# SCH.net
KiCad netlist of a schematic drawn in Altium Designer
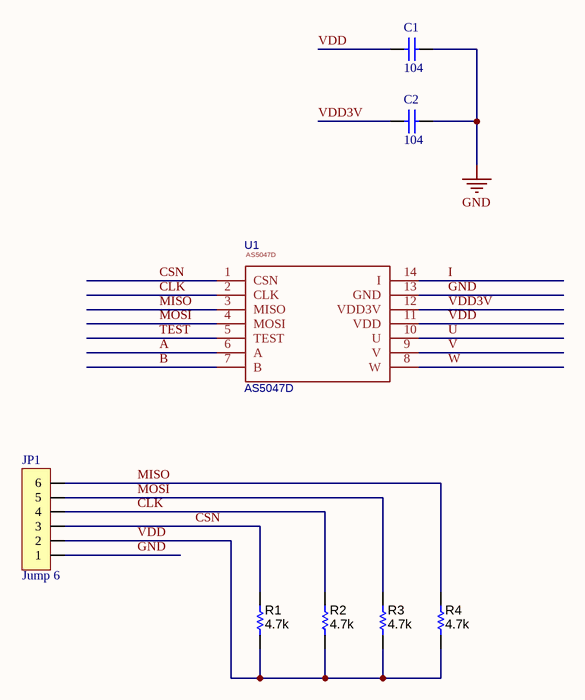
[diagram p0: SCH.SchDoc]

(export (version "E")
  (design (tool "Eeschema 10.0.6"))
  (components
    (comp (ref "C1")
      (value "104")
      (footprint "TU_SMD_0805")
      (description "Ceramic Chip Capacitor - Standard")
      (fields (field (name "PUBLISHER") "Altium Limited"))
      (libsource (lib "mySch") (part "Capacitor 0805"))
    )
    (comp (ref "C2")
      (value "104")
      (footprint "TU_SMD_0805")
      (description "Ceramic Chip Capacitor - Standard")
      (fields (field (name "PUBLISHER") "Altium Limited"))
      (libsource (lib "mySch") (part "Capacitor 0805"))
    )
    (comp (ref "JP1")
      (value "Jump 6")
      (footprint "ZH 1.5 6P")
      (description "Jump 6P 2.54")
      (libsource (lib "mySch") (part "Jump 6"))
    )
    (comp (ref "R1")
      (value "4.7k")
      (footprint "Tro SMD 0805")
      (description "RES, 100, 1%, 0.1 W, 0402")
      (fields
        (field (name "PARTNUMBER") "ERJ-2RKF1000X")
        (field (name "MANUFACTURER") "Panasonic")
        (field (name "PUBLISHER") "Texas Instruments")
      )
      (libsource (lib "mySch") (part "R nho"))
    )
    (comp (ref "R2")
      (value "4.7k")
      (footprint "Tro SMD 0805")
      (description "RES, 100, 1%, 0.1 W, 0402")
      (fields
        (field (name "PARTNUMBER") "ERJ-2RKF1000X")
        (field (name "MANUFACTURER") "Panasonic")
        (field (name "PUBLISHER") "Texas Instruments")
      )
      (libsource (lib "mySch") (part "R nho"))
    )
    (comp (ref "R3")
      (value "4.7k")
      (footprint "Tro SMD 0805")
      (description "RES, 100, 1%, 0.1 W, 0402")
      (fields
        (field (name "PARTNUMBER") "ERJ-2RKF1000X")
        (field (name "MANUFACTURER") "Panasonic")
        (field (name "PUBLISHER") "Texas Instruments")
      )
      (libsource (lib "mySch") (part "R nho"))
    )
    (comp (ref "R4")
      (value "4.7k")
      (footprint "Tro SMD 0805")
      (description "RES, 100, 1%, 0.1 W, 0402")
      (fields
        (field (name "PARTNUMBER") "ERJ-2RKF1000X")
        (field (name "MANUFACTURER") "Panasonic")
        (field (name "PUBLISHER") "Texas Instruments")
      )
      (libsource (lib "mySch") (part "R nho"))
    )
    (comp (ref "U1")
      (value "AS5047D")
      (footprint "TSSOP14")
      (fields (field (name "BOM_MANUFACTURER PART") "?"))
      (libsource (lib "mySch") (part "AS5047D"))
    )
  )
  (nets
    (net (code "1") (name "/A") (class "Default")
      (node (ref "U1") (pin "6") (pinfunction "A_6") (pintype "passive"))
    )
    (net (code "2") (name "/B") (class "Default")
      (node (ref "U1") (pin "7") (pinfunction "B_7") (pintype "passive"))
    )
    (net (code "3") (name "/CLK") (class "Default")
      (node (ref "JP1") (pin "4") (pinfunction "4_4") (pintype "passive"))
      (node (ref "R2") (pin "1") (pinfunction "1_1") (pintype "passive"))
      (node (ref "U1") (pin "2") (pinfunction "CLK_2") (pintype "passive"))
    )
    (net (code "4") (name "/CSN") (class "Default")
      (node (ref "JP1") (pin "3") (pinfunction "3_3") (pintype "passive"))
      (node (ref "R1") (pin "1") (pinfunction "1_1") (pintype "passive"))
      (node (ref "U1") (pin "1") (pinfunction "CSN_1") (pintype "passive"))
    )
    (net (code "5") (name "/I") (class "Default")
      (node (ref "U1") (pin "14") (pinfunction "I_14") (pintype "passive"))
    )
    (net (code "6") (name "/MISO") (class "Default")
      (node (ref "JP1") (pin "6") (pinfunction "6_6") (pintype "passive"))
      (node (ref "R4") (pin "1") (pinfunction "1_1") (pintype "passive"))
      (node (ref "U1") (pin "3") (pinfunction "MISO_3") (pintype "passive"))
    )
    (net (code "7") (name "/MOSI") (class "Default")
      (node (ref "JP1") (pin "5") (pinfunction "5_5") (pintype "passive"))
      (node (ref "R3") (pin "1") (pinfunction "1_1") (pintype "passive"))
      (node (ref "U1") (pin "4") (pinfunction "MOSI_4") (pintype "passive"))
    )
    (net (code "8") (name "/TEST") (class "Default")
      (node (ref "U1") (pin "5") (pinfunction "TEST_5") (pintype "passive"))
    )
    (net (code "9") (name "/U") (class "Default")
      (node (ref "U1") (pin "10") (pinfunction "U_10") (pintype "passive"))
    )
    (net (code "10") (name "/V") (class "Default")
      (node (ref "U1") (pin "9") (pinfunction "V_9") (pintype "passive"))
    )
    (net (code "11") (name "/VDD") (class "Default")
      (node (ref "C1") (pin "1") (pinfunction "1_1") (pintype "passive"))
      (node (ref "JP1") (pin "2") (pinfunction "2_2") (pintype "passive"))
      (node (ref "R1") (pin "2") (pinfunction "2_2") (pintype "passive"))
      (node (ref "R2") (pin "2") (pinfunction "2_2") (pintype "passive"))
      (node (ref "R3") (pin "2") (pinfunction "2_2") (pintype "passive"))
      (node (ref "R4") (pin "2") (pinfunction "2_2") (pintype "passive"))
      (node (ref "U1") (pin "11") (pinfunction "VDD_11") (pintype "passive"))
    )
    (net (code "12") (name "/VDD3V") (class "Default")
      (node (ref "C2") (pin "1") (pinfunction "1_1") (pintype "passive"))
      (node (ref "U1") (pin "12") (pinfunction "VDD3V_12") (pintype "passive"))
    )
    (net (code "13") (name "/W") (class "Default")
      (node (ref "U1") (pin "8") (pinfunction "W_8") (pintype "passive"))
    )
    (net (code "14") (name "GND") (class "Default")
      (node (ref "C1") (pin "2") (pinfunction "2_2") (pintype "passive"))
      (node (ref "C2") (pin "2") (pinfunction "2_2") (pintype "passive"))
      (node (ref "JP1") (pin "1") (pinfunction "1_1") (pintype "passive"))
      (node (ref "U1") (pin "13") (pinfunction "GND_13") (pintype "passive"))
    )
  )
)
